# DAU_Kupplung_1_phasig_V1_11.net
KiCad netlist of a schematic drawn in EAGLE
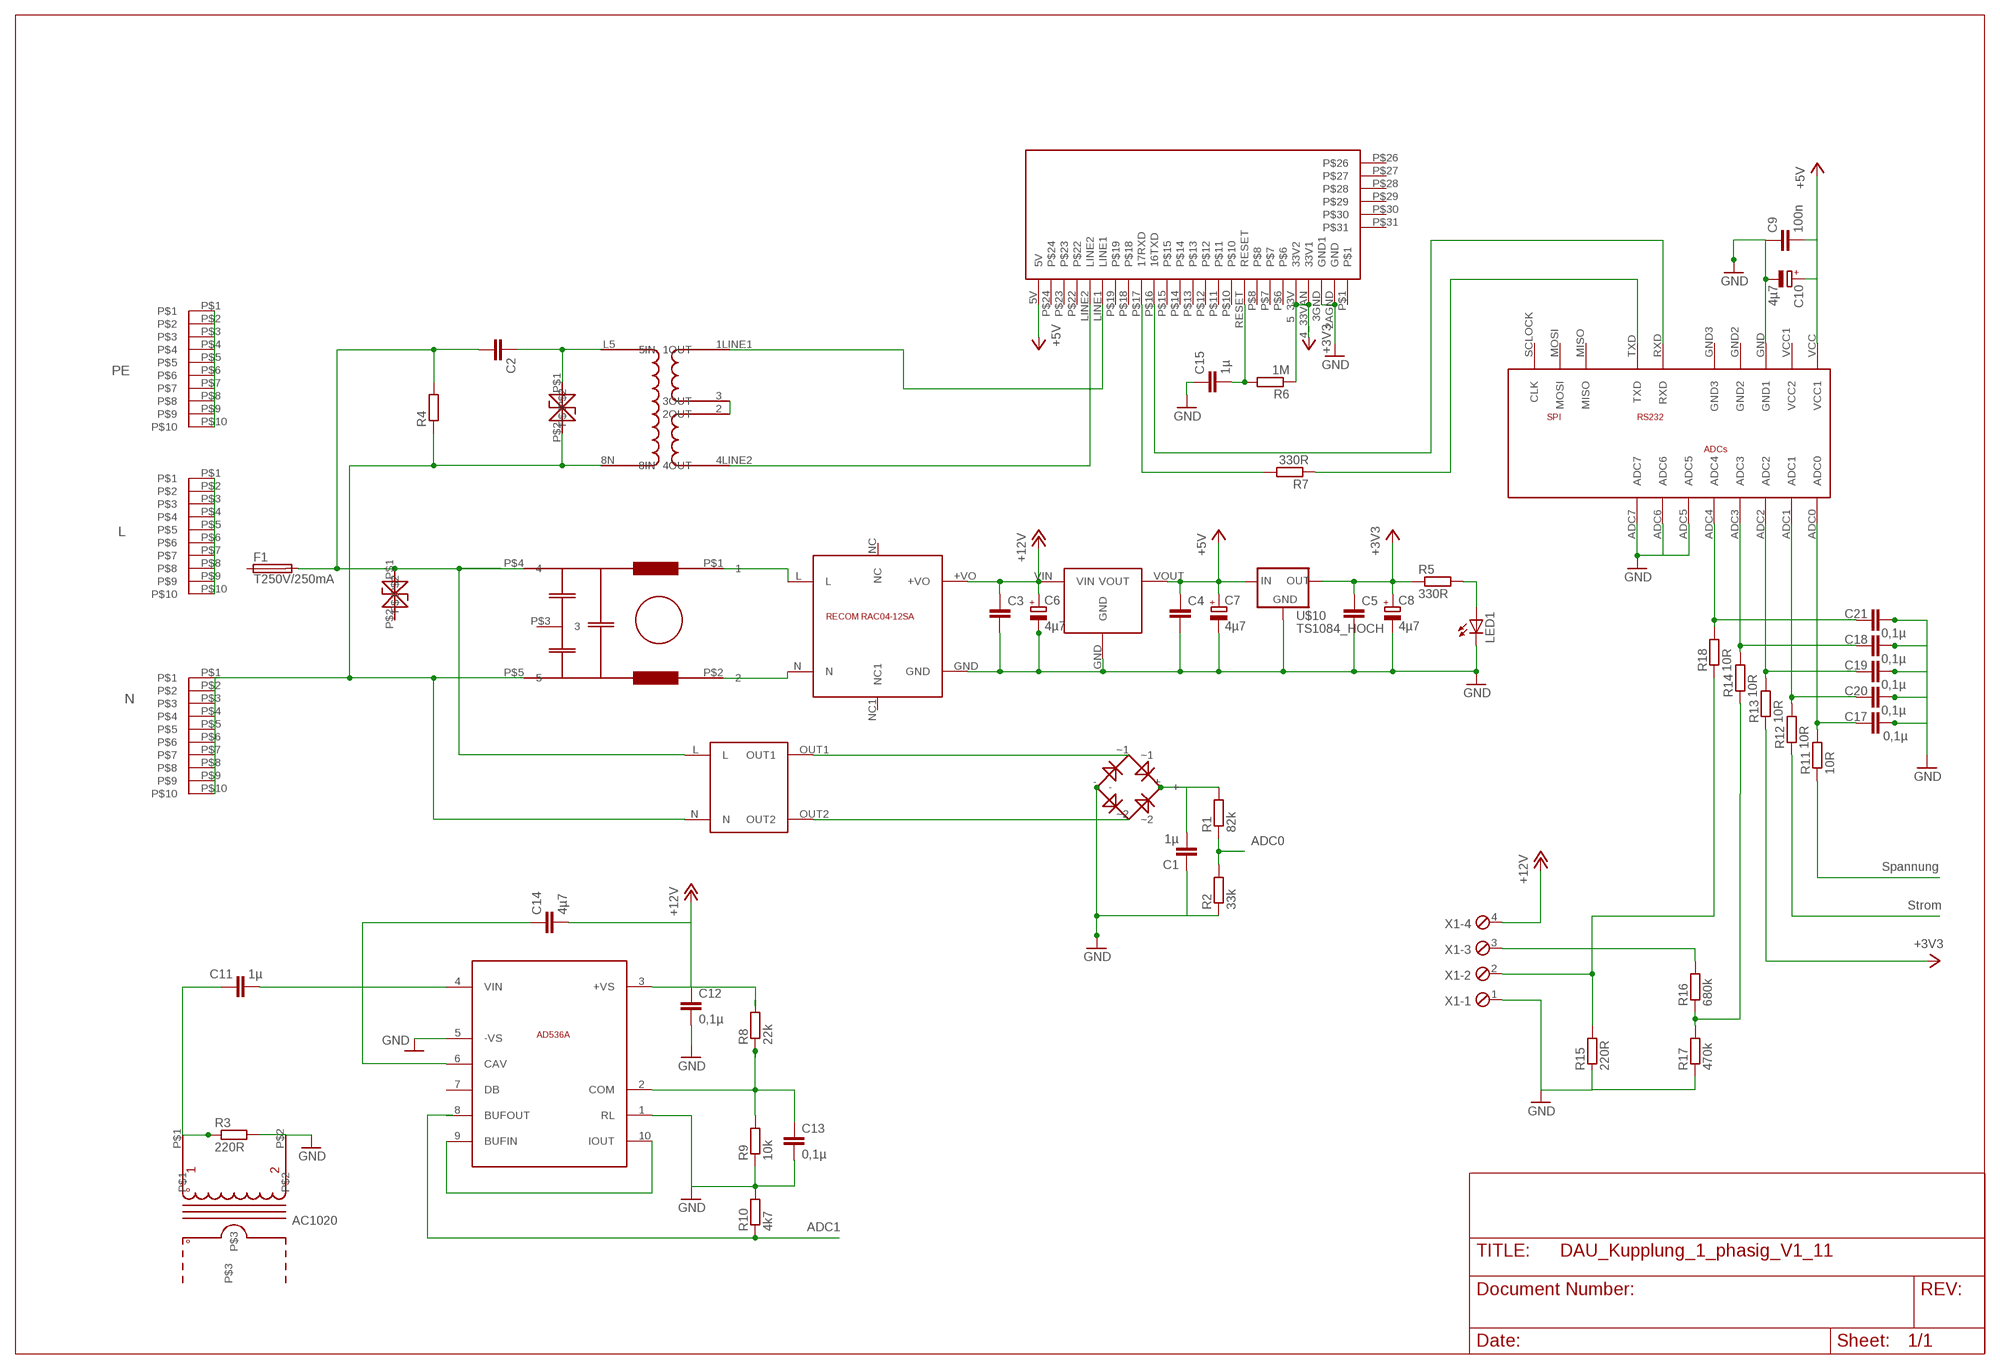
[diagram p0: schematic, sheet 1]

(export (version "E")
  (design (tool "Eeschema 10.0.6"))
  (components
    (comp (ref "AC1020")
      (value "AC1010")
      (footprint "eagle-import:AC1010")
      (libsource (lib "eagle-import") (part "AC1010"))
    )
    (comp (ref "C1")
      (value "1µ")
      (footprint "eagle-import:C2.5-3")
      (libsource (lib "eagle-import") (part "C2,5-3"))
    )
    (comp (ref "C2")
      (value "C-EU150-072X183")
      (footprint "eagle-import:C150-072X183")
      (libsource (lib "eagle-import") (part "resistor_C-EU150-072X183"))
    )
    (comp (ref "C3")
      (value "C-EUC0805")
      (footprint "eagle-import:C0805")
      (libsource (lib "eagle-import") (part "resistor_C-EUC0805"))
    )
    (comp (ref "C4")
      (value "C-EUC0805")
      (footprint "eagle-import:C0805")
      (libsource (lib "eagle-import") (part "resistor_C-EUC0805"))
    )
    (comp (ref "C5")
      (value "C-EUC0805")
      (footprint "eagle-import:C0805")
      (libsource (lib "eagle-import") (part "resistor_C-EUC0805"))
    )
    (comp (ref "C6")
      (value "4µ7")
      (footprint "eagle-import:E2-4")
      (libsource (lib "eagle-import") (part "CPOL-EUE2-4"))
    )
    (comp (ref "C7")
      (value "4µ7")
      (footprint "eagle-import:E2-4")
      (libsource (lib "eagle-import") (part "CPOL-EUE2-4"))
    )
    (comp (ref "C8")
      (value "4µ7")
      (footprint "eagle-import:E2-4")
      (libsource (lib "eagle-import") (part "CPOL-EUE2-4"))
    )
    (comp (ref "C9")
      (value "100n")
      (footprint "eagle-import:C0805")
      (libsource (lib "eagle-import") (part "C-EUC0805"))
    )
    (comp (ref "C10")
      (value "4µ7")
      (footprint "eagle-import:E2-4")
      (libsource (lib "eagle-import") (part "CPOL-EUE2-4"))
    )
    (comp (ref "C11")
      (value "1µ")
      (footprint "eagle-import:C0805")
      (libsource (lib "eagle-import") (part "C-EUC0805"))
    )
    (comp (ref "C12")
      (value "0,1µ")
      (footprint "eagle-import:C0805")
      (libsource (lib "eagle-import") (part "C-EUC0805"))
    )
    (comp (ref "C13")
      (value "0,1µ")
      (footprint "eagle-import:C0805")
      (libsource (lib "eagle-import") (part "C-EUC0805"))
    )
    (comp (ref "C14")
      (value "4µ7")
      (footprint "eagle-import:C0805")
      (libsource (lib "eagle-import") (part "C-EUC0805"))
    )
    (comp (ref "C15")
      (value "1µ")
      (footprint "eagle-import:C0805")
      (libsource (lib "eagle-import") (part "resistor_C-EUC0805"))
    )
    (comp (ref "C17")
      (value "0,1µ")
      (footprint "eagle-import:C0805")
      (libsource (lib "eagle-import") (part "resistor_C-EUC0805"))
    )
    (comp (ref "C18")
      (value "0,1µ")
      (footprint "eagle-import:C0805")
      (libsource (lib "eagle-import") (part "resistor_C-EUC0805"))
    )
    (comp (ref "C19")
      (value "0,1µ")
      (footprint "eagle-import:C0805")
      (libsource (lib "eagle-import") (part "resistor_C-EUC0805"))
    )
    (comp (ref "C20")
      (value "0,1µ")
      (footprint "eagle-import:C0805")
      (libsource (lib "eagle-import") (part "resistor_C-EUC0805"))
    )
    (comp (ref "C21")
      (value "0,1µ")
      (footprint "eagle-import:C0805")
      (libsource (lib "eagle-import") (part "resistor_C-EUC0805"))
    )
    (comp (ref "F1")
      (value "T250V/250mA")
      (footprint "eagle-import:TR5")
      (libsource (lib "eagle-import") (part "TR5"))
    )
    (comp (ref "L")
      (value "PRINT_CONNECTOR")
      (footprint "eagle-import:FASTON_DOUBLE")
      (libsource (lib "eagle-import") (part "PRINT_CONNECTOR"))
    )
    (comp (ref "LED1")
      (value "LEDSQR2X5")
      (footprint "eagle-import:LED2X5")
      (libsource (lib "eagle-import") (part "LEDSQR2X5"))
    )
    (comp (ref "N")
      (value "PRINT_CONNECTOR")
      (footprint "eagle-import:FASTON_DOUBLE")
      (libsource (lib "eagle-import") (part "PRINT_CONNECTOR"))
    )
    (comp (ref "PE")
      (value "PRINT_CONNECTOR")
      (footprint "eagle-import:FASTON_DOUBLE")
      (libsource (lib "eagle-import") (part "PRINT_CONNECTOR"))
    )
    (comp (ref "R1")
      (value "82k")
      (footprint "eagle-import:R1206")
      (libsource (lib "eagle-import") (part "R-EU_R1206"))
    )
    (comp (ref "R2")
      (value "33k")
      (footprint "eagle-import:R1206")
      (libsource (lib "eagle-import") (part "R-EU_R1206"))
    )
    (comp (ref "R3")
      (value "220R")
      (footprint "eagle-import:R1206")
      (libsource (lib "eagle-import") (part "R-EU_R1206"))
    )
    (comp (ref "R4")
      (value "R-EU_0204/7")
      (footprint "eagle-import:0204_7")
      (libsource (lib "eagle-import") (part "R-EU_0204/7"))
    )
    (comp (ref "R5")
      (value "330R")
      (footprint "eagle-import:R1206")
      (libsource (lib "eagle-import") (part "R-EU_R1206"))
    )
    (comp (ref "R6")
      (value "1M")
      (footprint "eagle-import:R1206")
      (libsource (lib "eagle-import") (part "R-EU_R1206"))
    )
    (comp (ref "R7")
      (value "330R")
      (footprint "eagle-import:R1206")
      (libsource (lib "eagle-import") (part "R-EU_R1206"))
    )
    (comp (ref "R8")
      (value "22k")
      (footprint "eagle-import:R1206")
      (libsource (lib "eagle-import") (part "R-EU_R1206"))
    )
    (comp (ref "R9")
      (value "10k")
      (footprint "eagle-import:R1206")
      (libsource (lib "eagle-import") (part "R-EU_R1206"))
    )
    (comp (ref "R10")
      (value "4k7")
      (footprint "eagle-import:R1206")
      (libsource (lib "eagle-import") (part "R-EU_R1206"))
    )
    (comp (ref "R11")
      (value "10R")
      (footprint "eagle-import:R1206")
      (libsource (lib "eagle-import") (part "R-EU_R1206"))
    )
    (comp (ref "R12")
      (value "10R")
      (footprint "eagle-import:R1206")
      (libsource (lib "eagle-import") (part "R-EU_R1206"))
    )
    (comp (ref "R13")
      (value "10R")
      (footprint "eagle-import:R1206")
      (libsource (lib "eagle-import") (part "R-EU_R1206"))
    )
    (comp (ref "R14")
      (value "10R")
      (footprint "eagle-import:R1206")
      (libsource (lib "eagle-import") (part "R-EU_R1206"))
    )
    (comp (ref "R15")
      (value "220R")
      (footprint "eagle-import:R1206")
      (libsource (lib "eagle-import") (part "R-EU_R1206"))
    )
    (comp (ref "R16")
      (value "680k")
      (footprint "eagle-import:R1206")
      (libsource (lib "eagle-import") (part "R-EU_R1206"))
    )
    (comp (ref "R17")
      (value "470k")
      (footprint "eagle-import:R1206")
      (libsource (lib "eagle-import") (part "R-EU_R1206"))
    )
    (comp (ref "R18")
      (value "10R")
      (footprint "eagle-import:R1206")
      (libsource (lib "eagle-import") (part "R-EU_R1206"))
    )
    (comp (ref "U$1")
      (value "RECOM_RAC04_12SA")
      (footprint "eagle-import:RAC04_12SA")
      (libsource (lib "eagle-import") (part "RECOM_RAC04_12SA"))
    )
    (comp (ref "U$2")
      (value "SICHERHEITSTRAFO")
      (footprint "eagle-import:TRAFO_0,35VA")
      (libsource (lib "eagle-import") (part "SICHERHEITSTRAFO"))
    )
    (comp (ref "U$3")
      (value "ADUC831_MINIMUM")
      (footprint "eagle-import:ADUC_MINIMUM")
      (libsource (lib "eagle-import") (part "ADUC831_MINIMUM"))
    )
    (comp (ref "U$4")
      (value "IT800")
      (footprint "eagle-import:IT800")
      (libsource (lib "eagle-import") (part "IT800"))
    )
    (comp (ref "U$5")
      (value "PLC_UEBERTRAGER_V2")
      (footprint "eagle-import:PLC-UEBERTRAGER_V2")
      (libsource (lib "eagle-import") (part "PLC_UEBERTRAGER_V2"))
    )
    (comp (ref "U$6")
      (value "NETZFILTER_24_25")
      (footprint "eagle-import:NETZFILTER_25_25")
      (libsource (lib "eagle-import") (part "NETZFILTER_24_25"))
    )
    (comp (ref "U$7")
      (value "AD536")
      (footprint "eagle-import:TO100_10PIN")
      (libsource (lib "eagle-import") (part "AD536"))
    )
    (comp (ref "U$8")
      (value "RECTIFIER")
      (footprint "eagle-import:RECTIFIER")
      (libsource (lib "eagle-import") (part "RECTIFIER"))
    )
    (comp (ref "U$9")
      (value "TSV")
      (footprint "eagle-import:TSV")
      (libsource (lib "eagle-import") (part "TSV"))
    )
    (comp (ref "U$10")
      (value "TS1084_HOCH")
      (footprint "eagle-import:TS1084_HOCH")
      (libsource (lib "eagle-import") (part "TS1084_HOCH"))
    )
    (comp (ref "U$11")
      (value "RECOM_785_05")
      (footprint "eagle-import:RECOM785X")
      (libsource (lib "eagle-import") (part "RECOM_785_05"))
    )
    (comp (ref "U$12")
      (value "TSV")
      (footprint "eagle-import:TSV")
      (libsource (lib "eagle-import") (part "TSV"))
    )
    (comp (ref "X1")
      (value "MPT4")
      (footprint "eagle-import:4POL254")
      (libsource (lib "eagle-import") (part "MPT4"))
    )
  )
  (nets
    (net (code "1") (name "+3V3") (class "Default")
      (node (ref "C5") (pin "1") (pinfunction "1_1") (pintype "passive"))
      (node (ref "C8") (pin "+") (pinfunction "+_+") (pintype "passive"))
      (node (ref "R13") (pin "1") (pinfunction "1_1") (pintype "passive"))
      (node (ref "R5") (pin "1") (pinfunction "1_1") (pintype "passive"))
      (node (ref "R6") (pin "1") (pinfunction "1_1") (pintype "passive"))
      (node (ref "U$10") (pin "OUT") (pinfunction "OUT_OUT") (pintype "passive"))
      (node (ref "U$4") (pin "4_33VAN") (pinfunction "33V1_4_33VAN") (pintype "bidirectional"))
      (node (ref "U$4") (pin "5_33V") (pinfunction "33V2_5_33V") (pintype "bidirectional"))
    )
    (net (code "2") (name "+5V") (class "Default")
      (node (ref "C10") (pin "+") (pinfunction "+_+") (pintype "passive"))
      (node (ref "C4") (pin "1") (pinfunction "1_1") (pintype "passive"))
      (node (ref "C7") (pin "+") (pinfunction "+_+") (pintype "passive"))
      (node (ref "C9") (pin "2") (pinfunction "2_2") (pintype "passive"))
      (node (ref "U$10") (pin "IN") (pinfunction "IN_IN") (pintype "input"))
      (node (ref "U$11") (pin "VOUT") (pinfunction "VOUT_VOUT") (pintype "bidirectional"))
      (node (ref "U$3") (pin "VCC") (pinfunction "VCC1_VCC") (pintype "bidirectional"))
      (node (ref "U$4") (pin "5V") (pinfunction "5V_5V") (pintype "bidirectional"))
    )
    (net (code "3") (name "+12V") (class "Default")
      (node (ref "C12") (pin "1") (pinfunction "1_1") (pintype "passive"))
      (node (ref "C14") (pin "2") (pinfunction "2_2") (pintype "passive"))
      (node (ref "C3") (pin "1") (pinfunction "1_1") (pintype "passive"))
      (node (ref "C6") (pin "+") (pinfunction "+_+") (pintype "passive"))
      (node (ref "R8") (pin "2") (pinfunction "2_2") (pintype "passive"))
      (node (ref "U$1") (pin "+VO") (pinfunction "+VO_+VO") (pintype "bidirectional"))
      (node (ref "U$11") (pin "VIN") (pinfunction "VIN_VIN") (pintype "bidirectional"))
      (node (ref "U$7") (pin "3") (pinfunction "+VS_3") (pintype "bidirectional"))
      (node (ref "X1") (pin "4") (pinfunction "1_4") (pintype "passive"))
    )
    (net (code "4") (name "/ADC0") (class "Default")
      (node (ref "R1") (pin "1") (pinfunction "1_1") (pintype "passive"))
      (node (ref "R11") (pin "1") (pinfunction "1_1") (pintype "passive"))
      (node (ref "R2") (pin "2") (pinfunction "2_2") (pintype "passive"))
    )
    (net (code "5") (name "/ADC1") (class "Default")
      (node (ref "R10") (pin "1") (pinfunction "1_1") (pintype "passive"))
      (node (ref "R12") (pin "1") (pinfunction "1_1") (pintype "passive"))
    )
    (net (code "6") (name "GND") (class "Default")
      (node (ref "AC1020") (pin "P$2") (pinfunction "P$2_P$2") (pintype "bidirectional"))
      (node (ref "C1") (pin "1") (pinfunction "1_1") (pintype "passive"))
      (node (ref "C10") (pin "-") (pinfunction "-_-") (pintype "passive"))
      (node (ref "C12") (pin "2") (pinfunction "2_2") (pintype "passive"))
      (node (ref "C13") (pin "2") (pinfunction "2_2") (pintype "passive"))
      (node (ref "C15") (pin "1") (pinfunction "1_1") (pintype "passive"))
      (node (ref "C17") (pin "2") (pinfunction "2_2") (pintype "passive"))
      (node (ref "C18") (pin "2") (pinfunction "2_2") (pintype "passive"))
      (node (ref "C19") (pin "2") (pinfunction "2_2") (pintype "passive"))
      (node (ref "C20") (pin "2") (pinfunction "2_2") (pintype "passive"))
      (node (ref "C21") (pin "2") (pinfunction "2_2") (pintype "passive"))
      (node (ref "C3") (pin "2") (pinfunction "2_2") (pintype "passive"))
      (node (ref "C4") (pin "2") (pinfunction "2_2") (pintype "passive"))
      (node (ref "C5") (pin "2") (pinfunction "2_2") (pintype "passive"))
      (node (ref "C6") (pin "-") (pinfunction "-_-") (pintype "passive"))
      (node (ref "C7") (pin "-") (pinfunction "-_-") (pintype "passive"))
      (node (ref "C8") (pin "-") (pinfunction "-_-") (pintype "passive"))
      (node (ref "C9") (pin "1") (pinfunction "1_1") (pintype "passive"))
      (node (ref "LED1") (pin "K") (pinfunction "C_K") (pintype "passive"))
      (node (ref "R10") (pin "2") (pinfunction "2_2") (pintype "passive"))
      (node (ref "R17") (pin "1") (pinfunction "1_1") (pintype "passive"))
      (node (ref "R2") (pin "1") (pinfunction "1_1") (pintype "passive"))
      (node (ref "R3") (pin "2") (pinfunction "2_2") (pintype "passive"))
      (node (ref "R9") (pin "1") (pinfunction "1_1") (pintype "passive"))
      (node (ref "U$1") (pin "GND") (pinfunction "GND_GND") (pintype "bidirectional"))
      (node (ref "U$10") (pin "GND") (pinfunction "GND_GND") (pintype "input"))
      (node (ref "U$11") (pin "GND") (pinfunction "GND_GND") (pintype "bidirectional"))
      (node (ref "U$3") (pin "ADC5") (pinfunction "ADC5_ADC5") (pintype "bidirectional"))
      (node (ref "U$3") (pin "ADC6") (pinfunction "ADC6_ADC6") (pintype "bidirectional"))
      (node (ref "U$3") (pin "ADC7") (pinfunction "ADC7_ADC7") (pintype "bidirectional"))
      (node (ref "U$3") (pin "GND") (pinfunction "GND1_GND") (pintype "bidirectional"))
      (node (ref "U$4") (pin "2AGND") (pinfunction "GND_2AGND") (pintype "bidirectional"))
      (node (ref "U$4") (pin "3GND") (pinfunction "GND1_3GND") (pintype "bidirectional"))
      (node (ref "U$7") (pin "1") (pinfunction "RL_1") (pintype "bidirectional"))
      (node (ref "U$7") (pin "5") (pinfunction "-VS_5") (pintype "bidirectional"))
      (node (ref "U$8") (pin "-") (pinfunction "-_-") (pintype "bidirectional"))
      (node (ref "X1") (pin "1") (pinfunction "1_1") (pintype "passive"))
    )
    (net (code "7") (name "Net-(AC1020-PadP$1)") (class "Default")
      (node (ref "AC1020") (pin "P$1") (pinfunction "P$1_P$1") (pintype "bidirectional"))
      (node (ref "C11") (pin "1") (pinfunction "1_1") (pintype "passive"))
      (node (ref "R3") (pin "1") (pinfunction "1_1") (pintype "passive"))
    )
    (net (code "8") (name "Net-(C1-Pad2)") (class "Default")
      (node (ref "C1") (pin "2") (pinfunction "2_2") (pintype "passive"))
      (node (ref "R1") (pin "2") (pinfunction "2_2") (pintype "passive"))
      (node (ref "U$8") (pin "+") (pinfunction "+_+") (pintype "bidirectional"))
    )
    (net (code "9") (name "Net-(C15-Pad2)") (class "Default")
      (node (ref "C15") (pin "2") (pinfunction "2_2") (pintype "passive"))
      (node (ref "R6") (pin "2") (pinfunction "2_2") (pintype "passive"))
      (node (ref "U$4") (pin "RESET") (pinfunction "RESET_RESET") (pintype "bidirectional"))
    )
    (net (code "10") (name "Net-(C17-Pad1)") (class "Default")
      (node (ref "C17") (pin "1") (pinfunction "1_1") (pintype "passive"))
      (node (ref "R11") (pin "2") (pinfunction "2_2") (pintype "passive"))
      (node (ref "U$3") (pin "ADC0") (pinfunction "ADC0_ADC0") (pintype "bidirectional"))
    )
    (net (code "11") (name "Net-(C18-Pad1)") (class "Default")
      (node (ref "C18") (pin "1") (pinfunction "1_1") (pintype "passive"))
      (node (ref "R14") (pin "2") (pinfunction "2_2") (pintype "passive"))
      (node (ref "U$3") (pin "ADC3") (pinfunction "ADC3_ADC3") (pintype "bidirectional"))
    )
    (net (code "12") (name "Net-(C19-Pad1)") (class "Default")
      (node (ref "C19") (pin "1") (pinfunction "1_1") (pintype "passive"))
      (node (ref "R13") (pin "2") (pinfunction "2_2") (pintype "passive"))
      (node (ref "U$3") (pin "ADC2") (pinfunction "ADC2_ADC2") (pintype "bidirectional"))
    )
    (net (code "13") (name "Net-(C20-Pad1)") (class "Default")
      (node (ref "C20") (pin "1") (pinfunction "1_1") (pintype "passive"))
      (node (ref "R12") (pin "2") (pinfunction "2_2") (pintype "passive"))
      (node (ref "U$3") (pin "ADC1") (pinfunction "ADC1_ADC1") (pintype "bidirectional"))
    )
    (net (code "14") (name "Net-(C21-Pad1)") (class "Default")
      (node (ref "C21") (pin "1") (pinfunction "1_1") (pintype "passive"))
      (node (ref "R18") (pin "2") (pinfunction "2_2") (pintype "passive"))
      (node (ref "U$3") (pin "ADC4") (pinfunction "ADC4_ADC4") (pintype "bidirectional"))
    )
    (net (code "15") (name "Net-(L-PadP$1)") (class "Default")
      (node (ref "L") (pin "P$1") (pinfunction "P$1_P$1") (pintype "bidirectional"))
      (node (ref "L") (pin "P$10") (pinfunction "P$10_P$10") (pintype "bidirectional"))
      (node (ref "L") (pin "P$2") (pinfunction "P$2_P$2") (pintype "bidirectional"))
      (node (ref "L") (pin "P$3") (pinfunction "P$3_P$3") (pintype "bidirectional"))
      (node (ref "L") (pin "P$4") (pinfunction "P$4_P$4") (pintype "bidirectional"))
      (node (ref "L") (pin "P$5") (pinfunction "P$5_P$5") (pintype "bidirectional"))
      (node (ref "L") (pin "P$6") (pinfunction "P$6_P$6") (pintype "bidirectional"))
      (node (ref "L") (pin "P$7") (pinfunction "P$7_P$7") (pintype "bidirectional"))
      (node (ref "L") (pin "P$8") (pinfunction "P$8_P$8") (pintype "bidirectional"))
      (node (ref "L") (pin "P$9") (pinfunction "P$9_P$9") (pintype "bidirectional"))
    )
    (net (code "16") (name "Net-(LED1-PadA)") (class "Default")
      (node (ref "LED1") (pin "A") (pinfunction "A_A") (pintype "passive"))
      (node (ref "R5") (pin "2") (pinfunction "2_2") (pintype "passive"))
    )
    (net (code "17") (name "Net-(PE-PadP$1)") (class "Default")
      (node (ref "PE") (pin "P$1") (pinfunction "P$1_P$1") (pintype "bidirectional"))
      (node (ref "PE") (pin "P$10") (pinfunction "P$10_P$10") (pintype "bidirectional"))
      (node (ref "PE") (pin "P$2") (pinfunction "P$2_P$2") (pintype "bidirectional"))
      (node (ref "PE") (pin "P$3") (pinfunction "P$3_P$3") (pintype "bidirectional"))
      (node (ref "PE") (pin "P$4") (pinfunction "P$4_P$4") (pintype "bidirectional"))
      (node (ref "PE") (pin "P$5") (pinfunction "P$5_P$5") (pintype "bidirectional"))
      (node (ref "PE") (pin "P$6") (pinfunction "P$6_P$6") (pintype "bidirectional"))
      (node (ref "PE") (pin "P$7") (pinfunction "P$7_P$7") (pintype "bidirectional"))
      (node (ref "PE") (pin "P$8") (pinfunction "P$8_P$8") (pintype "bidirectional"))
      (node (ref "PE") (pin "P$9") (pinfunction "P$9_P$9") (pintype "bidirectional"))
    )
    (net (code "18") (name "Net-(R7-Pad1)") (class "Default")
      (node (ref "R7") (pin "1") (pinfunction "1_1") (pintype "passive"))
      (node (ref "U$3") (pin "TXD") (pinfunction "TXD_TXD") (pintype "bidirectional"))
    )
    (net (code "19") (name "Net-(R14-Pad1)") (class "Default")
      (node (ref "R14") (pin "1") (pinfunction "1_1") (pintype "passive"))
      (node (ref "R16") (pin "1") (pinfunction "1_1") (pintype "passive"))
      (node (ref "R17") (pin "2") (pinfunction "2_2") (pintype "passive"))
    )
    (net (code "20") (name "Net-(U$4-16TXD)") (class "Default")
      (node (ref "U$3") (pin "RXD") (pinfunction "RXD_RXD") (pintype "bidirectional"))
      (node (ref "U$4") (pin "P$16") (pinfunction "16TXD_P$16") (pintype "bidirectional"))
    )
    (net (code "21") (name "Net-(U$4-17RXD)") (class "Default")
      (node (ref "R7") (pin "2") (pinfunction "2_2") (pintype "passive"))
      (node (ref "U$4") (pin "P$17") (pinfunction "17RXD_P$17") (pintype "bidirectional"))
    )
    (net (code "22") (name "Net-(U$5-1OUT)") (class "Default")
      (node (ref "U$4") (pin "LINE1") (pinfunction "LINE1_LINE1") (pintype "bidirectional"))
      (node (ref "U$5") (pin "1LINE1") (pinfunction "1OUT_1LINE1") (pintype "output"))
    )
    (net (code "23") (name "Net-(U$5-2OUT)") (class "Default")
      (node (ref "U$5") (pin "2") (pinfunction "2OUT_2") (pintype "output"))
      (node (ref "U$5") (pin "3") (pinfunction "3OUT_3") (pintype "output"))
    )
    (net (code "24") (name "Net-(U$5-4OUT)") (class "Default")
      (node (ref "U$4") (pin "LINE2") (pinfunction "LINE2_LINE2") (pintype "bidirectional"))
      (node (ref "U$5") (pin "4LINE2") (pinfunction "4OUT_4LINE2") (pintype "output"))
    )
    (net (code "25") (name "Net-(U$5-5IN)") (class "Default")
      (node (ref "C2") (pin "1") (pinfunction "1_1") (pintype "passive"))
      (node (ref "U$12") (pin "P$1") (pinfunction "P$1_P$1") (pintype "bidirectional"))
      (node (ref "U$5") (pin "L5") (pinfunction "5IN_L5") (pintype "input"))
    )
    (net (code "26") (name "Net-(U$5-8IN)") (class "Default")
      (node (ref "N") (pin "P$1") (pinfunction "P$1_P$1") (pintype "bidirectional"))
      (node (ref "N") (pin "P$10") (pinfunction "P$10_P$10") (pintype "bidirectional"))
      (node (ref "N") (pin "P$2") (pinfunction "P$2_P$2") (pintype "bidirectional"))
      (node (ref "N") (pin "P$3") (pinfunction "P$3_P$3") (pintype "bidirectional"))
      (node (ref "N") (pin "P$4") (pinfunction "P$4_P$4") (pintype "bidirectional"))
      (node (ref "N") (pin "P$5") (pinfunction "P$5_P$5") (pintype "bidirectional"))
      (node (ref "N") (pin "P$6") (pinfunction "P$6_P$6") (pintype "bidirectional"))
      (node (ref "N") (pin "P$7") (pinfunction "P$7_P$7") (pintype "bidirectional"))
      (node (ref "N") (pin "P$8") (pinfunction "P$8_P$8") (pintype "bidirectional"))
      (node (ref "N") (pin "P$9") (pinfunction "P$9_P$9") (pintype "bidirectional"))
      (node (ref "R4") (pin "1") (pinfunction "1_1") (pintype "passive"))
      (node (ref "U$12") (pin "P$2") (pinfunction "P$2_P$2") (pintype "bidirectional"))
      (node (ref "U$2") (pin "N") (pinfunction "N_N") (pintype "bidirectional"))
      (node (ref "U$5") (pin "8N") (pinfunction "8IN_8N") (pintype "input"))
      (node (ref "U$6") (pin "P$5") (pinfunction "5_P$5") (pintype "bidirectional"))
    )
    (net (code "27") (name "Net-(U$6-1)") (class "Default")
      (node (ref "U$1") (pin "L") (pinfunction "L_L") (pintype "bidirectional"))
      (node (ref "U$6") (pin "P$1") (pinfunction "1_P$1") (pintype "bidirectional"))
    )
    (net (code "28") (name "Net-(U$6-2)") (class "Default")
      (node (ref "U$1") (pin "N") (pinfunction "N_N") (pintype "bidirectional"))
      (node (ref "U$6") (pin "P$2") (pinfunction "2_P$2") (pintype "bidirectional"))
    )
    (net (code "29") (name "Net-(U$6-4)") (class "Default")
      (node (ref "C2") (pin "2") (pinfunction "2_2") (pintype "passive"))
      (node (ref "F1") (pin "2") (pinfunction "2_2") (pintype "passive"))
      (node (ref "R4") (pin "2") (pinfunction "2_2") (pintype "passive"))
      (node (ref "U$2") (pin "L") (pinfunction "L_L") (pintype "bidirectional"))
      (node (ref "U$6") (pin "P$4") (pinfunction "4_P$4") (pintype "bidirectional"))
      (node (ref "U$9") (pin "P$1") (pinfunction "P$1_P$1") (pintype "bidirectional"))
    )
    (net (code "30") (name "Net-(U$7-BUFIN)") (class "Default")
      (node (ref "U$7") (pin "10") (pinfunction "IOUT_10") (pintype "bidirectional"))
      (node (ref "U$7") (pin "9") (pinfunction "BUFIN_9") (pintype "bidirectional"))
    )
    (net (code "31") (name "Net-(U$7-CAV)") (class "Default")
      (node (ref "C14") (pin "1") (pinfunction "1_1") (pintype "passive"))
      (node (ref "U$7") (pin "6") (pinfunction "CAV_6") (pintype "bidirectional"))
    )
    (net (code "32") (name "Net-(U$7-COM)") (class "Default")
      (node (ref "C13") (pin "1") (pinfunction "1_1") (pintype "passive"))
      (node (ref "R8") (pin "1") (pinfunction "1_1") (pintype "passive"))
      (node (ref "R9") (pin "2") (pinfunction "2_2") (pintype "passive"))
      (node (ref "U$7") (pin "2") (pinfunction "COM_2") (pintype "bidirectional"))
    )
    (net (code "33") (name "Net-(U$7-VIN)") (class "Default")
      (node (ref "C11") (pin "2") (pinfunction "2_2") (pintype "passive"))
      (node (ref "U$7") (pin "4") (pinfunction "VIN_4") (pintype "bidirectional"))
    )
    (net (code "34") (name "Net-(U$8-~{1})") (class "Default")
      (node (ref "U$2") (pin "OUT1") (pinfunction "OUT1_OUT1") (pintype "bidirectional"))
      (node (ref "U$8") (pin "~1") (pinfunction "~{1}_~1") (pintype "bidirectional"))
    )
    (net (code "35") (name "Net-(U$8-~{2})") (class "Default")
      (node (ref "U$2") (pin "OUT2") (pinfunction "OUT2_OUT2") (pintype "bidirectional"))
      (node (ref "U$8") (pin "~2") (pinfunction "~{2}_~2") (pintype "bidirectional"))
    )
    (net (code "36") (name "Net-(X1B-1)") (class "Default")
      (node (ref "R15") (pin "2") (pinfunction "2_2") (pintype "passive"))
      (node (ref "R18") (pin "1") (pinfunction "1_1") (pintype "passive"))
      (node (ref "X1") (pin "2") (pinfunction "1_2") (pintype "passive"))
    )
    (net (code "37") (name "Net-(X1C-1)") (class "Default")
      (node (ref "R16") (pin "2") (pinfunction "2_2") (pintype "passive"))
      (node (ref "X1") (pin "3") (pinfunction "1_3") (pintype "passive"))
    )
    (net (code "38") (name "unconnected-(AC1020-PadP$3)") (class "Default")
      (node (ref "AC1020") (pin "P$3") (pinfunction "P$3_P$3") (pintype "bidirectional"))
    )
    (net (code "39") (name "unconnected-(F1-Pad1)") (class "Default")
      (node (ref "F1") (pin "1") (pinfunction "1_1") (pintype "passive"))
    )
    (net (code "40") (name "unconnected-(R15-Pad1)") (class "Default")
      (node (ref "R15") (pin "1") (pinfunction "1_1") (pintype "passive"))
    )
    (net (code "41") (name "unconnected-(U$1-PadNC)") (class "Default")
      (node (ref "U$1") (pin "NC") (pinfunction "NC_NC") (pintype "bidirectional"))
    )
    (net (code "42") (name "unconnected-(U$1-PadNC1)") (class "Default")
      (node (ref "U$1") (pin "NC1") (pinfunction "NC1_NC1") (pintype "bidirectional"))
    )
    (net (code "43") (name "unconnected-(U$3-CLK-PadSCLOCK)") (class "Default")
      (node (ref "U$3") (pin "SCLOCK") (pinfunction "CLK_SCLOCK") (pintype "bidirectional"))
    )
    (net (code "44") (name "unconnected-(U$3-PadGND2)") (class "Default")
      (node (ref "U$3") (pin "GND2") (pinfunction "GND2_GND2") (pintype "bidirectional"))
    )
    (net (code "45") (name "unconnected-(U$3-PadGND3)") (class "Default")
      (node (ref "U$3") (pin "GND3") (pinfunction "GND3_GND3") (pintype "bidirectional"))
    )
    (net (code "46") (name "unconnected-(U$3-PadMISO)") (class "Default")
      (node (ref "U$3") (pin "MISO") (pinfunction "MISO_MISO") (pintype "bidirectional"))
    )
    (net (code "47") (name "unconnected-(U$3-PadMOSI)") (class "Default")
      (node (ref "U$3") (pin "MOSI") (pinfunction "MOSI_MOSI") (pintype "bidirectional"))
    )
    (net (code "48") (name "unconnected-(U$3-VCC2-PadVCC1)") (class "Default")
      (node (ref "U$3") (pin "VCC1") (pinfunction "VCC2_VCC1") (pintype "bidirectional"))
    )
    (net (code "49") (name "unconnected-(U$4-PadP$1)") (class "Default")
      (node (ref "U$4") (pin "P$1") (pinfunction "P$1_P$1") (pintype "bidirectional"))
    )
    (net (code "50") (name "unconnected-(U$4-PadP$6)") (class "Default")
      (node (ref "U$4") (pin "P$6") (pinfunction "P$6_P$6") (pintype "bidirectional"))
    )
    (net (code "51") (name "unconnected-(U$4-PadP$7)") (class "Default")
      (node (ref "U$4") (pin "P$7") (pinfunction "P$7_P$7") (pintype "bidirectional"))
    )
    (net (code "52") (name "unconnected-(U$4-PadP$8)") (class "Default")
      (node (ref "U$4") (pin "P$8") (pinfunction "P$8_P$8") (pintype "bidirectional"))
    )
    (net (code "53") (name "unconnected-(U$4-PadP$10)") (class "Default")
      (node (ref "U$4") (pin "P$10") (pinfunction "P$10_P$10") (pintype "bidirectional"))
    )
    (net (code "54") (name "unconnected-(U$4-PadP$11)") (class "Default")
      (node (ref "U$4") (pin "P$11") (pinfunction "P$11_P$11") (pintype "bidirectional"))
    )
    (net (code "55") (name "unconnected-(U$4-PadP$12)") (class "Default")
      (node (ref "U$4") (pin "P$12") (pinfunction "P$12_P$12") (pintype "bidirectional"))
    )
    (net (code "56") (name "unconnected-(U$4-PadP$13)") (class "Default")
      (node (ref "U$4") (pin "P$13") (pinfunction "P$13_P$13") (pintype "bidirectional"))
    )
    (net (code "57") (name "unconnected-(U$4-PadP$14)") (class "Default")
      (node (ref "U$4") (pin "P$14") (pinfunction "P$14_P$14") (pintype "bidirectional"))
    )
    (net (code "58") (name "unconnected-(U$4-PadP$15)") (class "Default")
      (node (ref "U$4") (pin "P$15") (pinfunction "P$15_P$15") (pintype "bidirectional"))
    )
    (net (code "59") (name "unconnected-(U$4-PadP$18)") (class "Default")
      (node (ref "U$4") (pin "P$18") (pinfunction "P$18_P$18") (pintype "bidirectional"))
    )
    (net (code "60") (name "unconnected-(U$4-PadP$19)") (class "Default")
      (node (ref "U$4") (pin "P$19") (pinfunction "P$19_P$19") (pintype "bidirectional"))
    )
    (net (code "61") (name "unconnected-(U$4-PadP$22)") (class "Default")
      (node (ref "U$4") (pin "P$22") (pinfunction "P$22_P$22") (pintype "bidirectional"))
    )
    (net (code "62") (name "unconnected-(U$4-PadP$23)") (class "Default")
      (node (ref "U$4") (pin "P$23") (pinfunction "P$23_P$23") (pintype "bidirectional"))
    )
    (net (code "63") (name "unconnected-(U$4-PadP$24)") (class "Default")
      (node (ref "U$4") (pin "P$24") (pinfunction "P$24_P$24") (pintype "bidirectional"))
    )
    (net (code "64") (name "unconnected-(U$4-PadP$26)") (class "Default")
      (node (ref "U$4") (pin "P$26") (pinfunction "P$26_P$26") (pintype "bidirectional"))
    )
    (net (code "65") (name "unconnected-(U$4-PadP$27)") (class "Default")
      (node (ref "U$4") (pin "P$27") (pinfunction "P$27_P$27") (pintype "bidirectional"))
    )
    (net (code "66") (name "unconnected-(U$4-PadP$28)") (class "Default")
      (node (ref "U$4") (pin "P$28") (pinfunction "P$28_P$28") (pintype "bidirectional"))
    )
    (net (code "67") (name "unconnected-(U$4-PadP$29)") (class "Default")
      (node (ref "U$4") (pin "P$29") (pinfunction "P$29_P$29") (pintype "bidirectional"))
    )
    (net (code "68") (name "unconnected-(U$4-PadP$30)") (class "Default")
      (node (ref "U$4") (pin "P$30") (pinfunction "P$30_P$30") (pintype "bidirectional"))
    )
    (net (code "69") (name "unconnected-(U$4-PadP$31)") (class "Default")
      (node (ref "U$4") (pin "P$31") (pinfunction "P$31_P$31") (pintype "bidirectional"))
    )
    (net (code "70") (name "unconnected-(U$6-3-PadP$3)") (class "Default")
      (node (ref "U$6") (pin "P$3") (pinfunction "3_P$3") (pintype "bidirectional"))
    )
    (net (code "71") (name "unconnected-(U$7-BUFOUT-Pad8)") (class "Default")
      (node (ref "U$7") (pin "8") (pinfunction "BUFOUT_8") (pintype "bidirectional"))
    )
    (net (code "72") (name "unconnected-(U$7-DB-Pad7)") (class "Default")
      (node (ref "U$7") (pin "7") (pinfunction "DB_7") (pintype "bidirectional"))
    )
    (net (code "73") (name "unconnected-(U$9-PadP$2)") (class "Default")
      (node (ref "U$9") (pin "P$2") (pinfunction "P$2_P$2") (pintype "bidirectional"))
    )
  )
)
